# canset_pcb.net
KiCad netlist of a schematic drawn in EAGLE
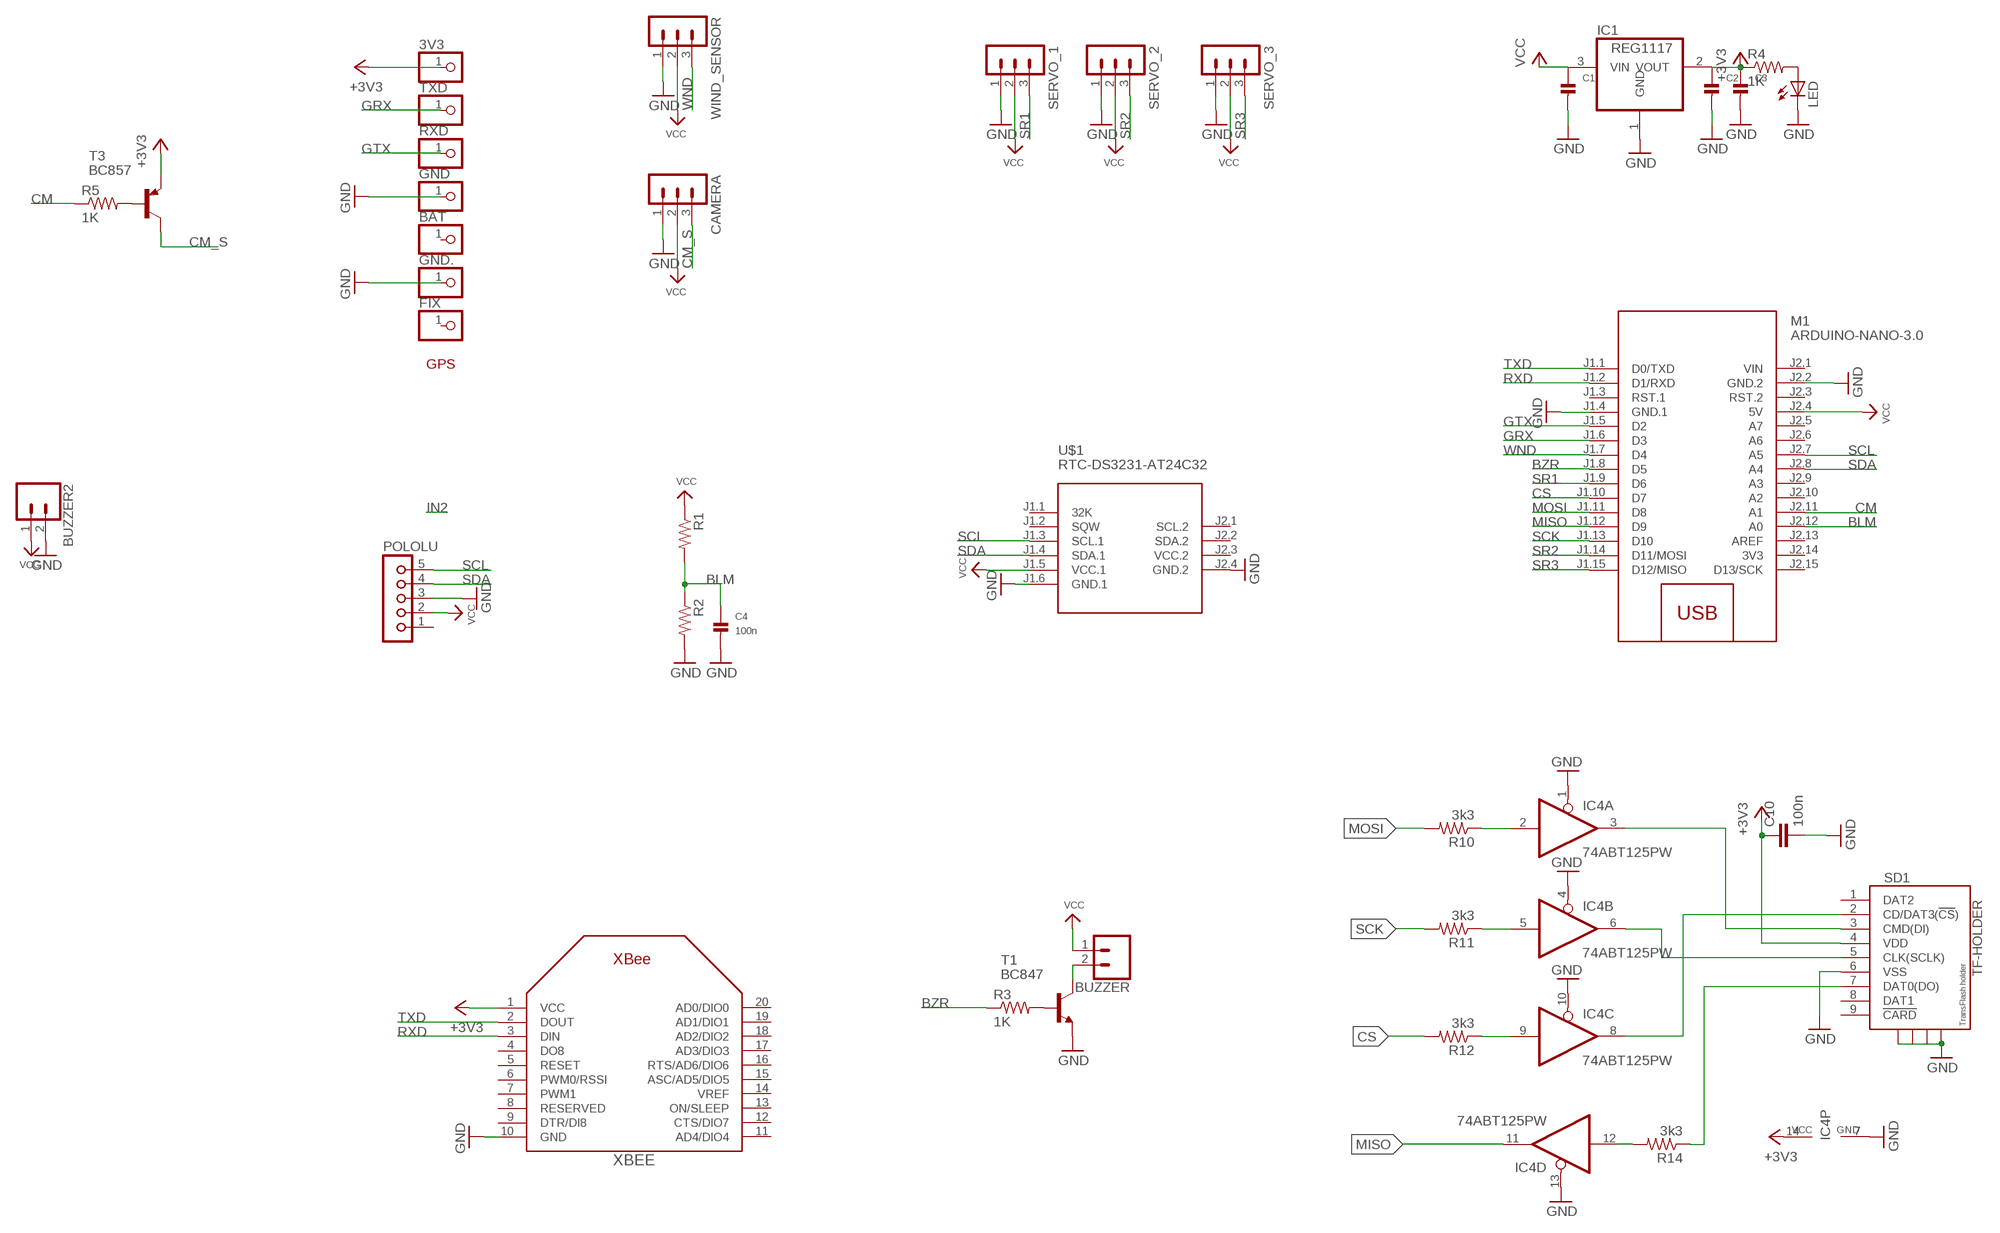
[diagram p0: schematic, sheet 1]

(export (version "E")
  (design (tool "Eeschema 10.0.6"))
  (components
    (comp (ref "3V3")
      (value "PINHD-1X1")
      (footprint "eagle-import:1X01")
      (libsource (lib "eagle-import") (part "PINHD-1X1"))
    )
    (comp (ref "BAT")
      (value "PINHD-1X1")
      (footprint "eagle-import:1X01")
      (libsource (lib "eagle-import") (part "PINHD-1X1"))
    )
    (comp (ref "BUZZER")
      (value "CONN_02")
      (footprint "eagle-import:1X02")
      (libsource (lib "eagle-import") (part "CONN_02"))
    )
    (comp (ref "BUZZER2")
      (value "CONN_02")
      (footprint "eagle-import:1X02")
      (libsource (lib "eagle-import") (part "CONN_02"))
    )
    (comp (ref "C1")
      (value "CAP_CERAMIC_0805")
      (footprint "eagle-import:_0805")
      (libsource (lib "eagle-import") (part "CAP_CERAMIC_0805"))
    )
    (comp (ref "C2")
      (value "CAP_CERAMIC_0805")
      (footprint "eagle-import:_0805")
      (libsource (lib "eagle-import") (part "CAP_CERAMIC_0805"))
    )
    (comp (ref "C3")
      (value "CAP_CERAMIC_0805")
      (footprint "eagle-import:_0805")
      (libsource (lib "eagle-import") (part "CAP_CERAMIC_0805"))
    )
    (comp (ref "C4")
      (value "100n")
      (footprint "eagle-import:_0805")
      (libsource (lib "eagle-import") (part "CAP_CERAMIC_0805"))
    )
    (comp (ref "C10")
      (value "100n")
      (footprint "eagle-import:C0603")
      (libsource (lib "eagle-import") (part "C-EUC0603"))
    )
    (comp (ref "CAMERA")
      (value "MA03-1")
      (footprint "eagle-import:MA03-1")
      (libsource (lib "eagle-import") (part "MA03-1"))
    )
    (comp (ref "FIX")
      (value "PINHD-1X1")
      (footprint "eagle-import:1X01")
      (libsource (lib "eagle-import") (part "PINHD-1X1"))
    )
    (comp (ref "GND")
      (value "PINHD-1X1")
      (footprint "eagle-import:1X01")
      (libsource (lib "eagle-import") (part "PINHD-1X1"))
    )
    (comp (ref "GND.")
      (value "PINHD-1X1")
      (footprint "eagle-import:1X01")
      (libsource (lib "eagle-import") (part "PINHD-1X1"))
    )
    (comp (ref "IC1")
      (value "REG1117")
      (footprint "eagle-import:SOT223")
      (libsource (lib "eagle-import") (part "REG1117"))
    )
    (comp (ref "IC4")
      (value "74ABT125PW")
      (footprint "eagle-import:TSSOP14")
      (libsource (lib "eagle-import") (part "74125PWABT"))
    )
    (comp (ref "LED")
      (value "LED5MM")
      (footprint "eagle-import:LED5MM")
      (libsource (lib "eagle-import") (part "LED5MM"))
    )
    (comp (ref "M1")
      (value "ARDUINO-NANO-3.0")
      (footprint "eagle-import:ARDUINO-NANO-3.0")
      (libsource (lib "eagle-import") (part "ARDUINO-NANO-3.0"))
    )
    (comp (ref "POLOLU")
      (value "JU05")
      (footprint "eagle-import:JU05")
      (libsource (lib "eagle-import") (part "JU05"))
    )
    (comp (ref "R1")
      (value "R-US_M0805")
      (footprint "eagle-import:M0805")
      (libsource (lib "eagle-import") (part "R-US_M0805"))
    )
    (comp (ref "R2")
      (value "R-US_M0805")
      (footprint "eagle-import:M0805")
      (libsource (lib "eagle-import") (part "R-US_M0805"))
    )
    (comp (ref "R3")
      (value "1K")
      (footprint "eagle-import:M0805")
      (libsource (lib "eagle-import") (part "R-US_M0805"))
    )
    (comp (ref "R4")
      (value "1K")
      (footprint "eagle-import:M0805")
      (libsource (lib "eagle-import") (part "R-US_M0805"))
    )
    (comp (ref "R5")
      (value "1K")
      (footprint "eagle-import:M0805")
      (libsource (lib "eagle-import") (part "R-US_M0805"))
    )
    (comp (ref "R10")
      (value "3k3")
      (footprint "eagle-import:R0603")
      (libsource (lib "eagle-import") (part "R-US_R0603"))
    )
    (comp (ref "R11")
      (value "3k3")
      (footprint "eagle-import:R0603")
      (libsource (lib "eagle-import") (part "R-US_R0603"))
    )
    (comp (ref "R12")
      (value "3k3")
      (footprint "eagle-import:R0603")
      (libsource (lib "eagle-import") (part "R-US_R0603"))
    )
    (comp (ref "R14")
      (value "3k3")
      (footprint "eagle-import:R0603")
      (libsource (lib "eagle-import") (part "R-US_R0603"))
    )
    (comp (ref "RXD")
      (value "PINHD-1X1")
      (footprint "eagle-import:1X01")
      (libsource (lib "eagle-import") (part "PINHD-1X1"))
    )
    (comp (ref "SD1")
      (value "TF-HOLDER")
      (footprint "eagle-import:TF-PULL")
      (libsource (lib "eagle-import") (part "TF-HOLDER"))
    )
    (comp (ref "SERVO_1")
      (value "MA03-1")
      (footprint "eagle-import:MA03-1")
      (libsource (lib "eagle-import") (part "MA03-1"))
    )
    (comp (ref "SERVO_2")
      (value "MA03-1")
      (footprint "eagle-import:MA03-1")
      (libsource (lib "eagle-import") (part "MA03-1"))
    )
    (comp (ref "SERVO_3")
      (value "MA03-1")
      (footprint "eagle-import:MA03-1")
      (libsource (lib "eagle-import") (part "MA03-1"))
    )
    (comp (ref "T1")
      (value "BC847")
      (footprint "eagle-import:SOT23")
      (libsource (lib "eagle-import") (part "BC847"))
    )
    (comp (ref "T3")
      (value "BC857")
      (footprint "eagle-import:SOT23")
      (libsource (lib "eagle-import") (part "BC857"))
    )
    (comp (ref "TXD")
      (value "PINHD-1X1")
      (footprint "eagle-import:1X01")
      (libsource (lib "eagle-import") (part "PINHD-1X1"))
    )
    (comp (ref "U$1")
      (value "RTC-DS3231-AT24C32")
      (footprint "eagle-import:RTC-DS3231-AT24C32")
      (libsource (lib "eagle-import") (part "RTC-DS3231-AT24C32"))
    )
    (comp (ref "WIND_SENSOR")
      (value "MA03-1")
      (footprint "eagle-import:MA03-1")
      (libsource (lib "eagle-import") (part "MA03-1"))
    )
    (comp (ref "XBEE")
      (value "XBEE")
      (footprint "eagle-import:XBEE")
      (libsource (lib "eagle-import") (part "XBEE"))
    )
  )
  (nets
    (net (code "1") (name "+3V3") (class "Default")
      (node (ref "3V3") (pin "1") (pinfunction "1_1") (pintype "passive"))
      (node (ref "C10") (pin "1") (pinfunction "1_1") (pintype "passive"))
      (node (ref "C2") (pin "1") (pinfunction "P$1_1") (pintype "passive"))
      (node (ref "C3") (pin "1") (pinfunction "P$1_1") (pintype "passive"))
      (node (ref "IC1") (pin "2") (pinfunction "VOUT_2") (pintype "output"))
      (node (ref "IC4") (pin "14") (pinfunction "VCC_14") (pintype "power_in"))
      (node (ref "R4") (pin "1") (pinfunction "1_1") (pintype "passive"))
      (node (ref "SD1") (pin "4") (pinfunction "VDD_4") (pintype "power_in"))
      (node (ref "T3") (pin "2") (pinfunction "E_2") (pintype "passive"))
      (node (ref "XBEE") (pin "1") (pinfunction "VCC_1") (pintype "power_in"))
    )
    (net (code "2") (name "/3V3") (class "Default")
      (node (ref "M1") (pin "J2.14") (pinfunction "3V3_J2.14") (pintype "power_in"))
    )
    (net (code "3") (name "/BLM") (class "Default")
      (node (ref "C4") (pin "1") (pinfunction "P$1_1") (pintype "passive"))
      (node (ref "M1") (pin "J2.12") (pinfunction "A0_J2.12") (pintype "bidirectional"))
      (node (ref "R1") (pin "2") (pinfunction "2_2") (pintype "passive"))
      (node (ref "R2") (pin "1") (pinfunction "1_1") (pintype "passive"))
    )
    (net (code "4") (name "/BZR") (class "Default")
      (node (ref "M1") (pin "J1.8") (pinfunction "D5_J1.8") (pintype "bidirectional"))
      (node (ref "R3") (pin "1") (pinfunction "1_1") (pintype "passive"))
    )
    (net (code "5") (name "/CM") (class "Default")
      (node (ref "M1") (pin "J2.11") (pinfunction "A1_J2.11") (pintype "bidirectional"))
      (node (ref "R5") (pin "1") (pinfunction "1_1") (pintype "passive"))
    )
    (net (code "6") (name "/CM_S") (class "Default")
      (node (ref "CAMERA") (pin "3") (pinfunction "3_3") (pintype "passive"))
      (node (ref "T3") (pin "3") (pinfunction "C_3") (pintype "passive"))
    )
    (net (code "7") (name "/GRX") (class "Default")
      (node (ref "M1") (pin "J1.6") (pinfunction "D3_J1.6") (pintype "bidirectional"))
      (node (ref "TXD") (pin "1") (pinfunction "1_1") (pintype "passive"))
    )
    (net (code "8") (name "/GTX") (class "Default")
      (node (ref "M1") (pin "J1.5") (pinfunction "D2_J1.5") (pintype "bidirectional"))
      (node (ref "RXD") (pin "1") (pinfunction "1_1") (pintype "passive"))
    )
    (net (code "10") (name "/RXD") (class "Default")
      (node (ref "M1") (pin "J1.2") (pinfunction "D1/RXD_J1.2") (pintype "bidirectional"))
      (node (ref "XBEE") (pin "3") (pinfunction "DIN_3") (pintype "input"))
    )
    (net (code "11") (name "/SCL") (class "Default")
      (node (ref "M1") (pin "J2.7") (pinfunction "A5_J2.7") (pintype "bidirectional"))
      (node (ref "POLOLU") (pin "5") (pinfunction "5_5") (pintype "passive"))
      (node (ref "U$1") (pin "J1.3") (pinfunction "SCL.1_J1.3") (pintype "bidirectional"))
    )
    (net (code "12") (name "/SDA") (class "Default")
      (node (ref "M1") (pin "J2.8") (pinfunction "A4_J2.8") (pintype "bidirectional"))
      (node (ref "POLOLU") (pin "4") (pinfunction "4_4") (pintype "passive"))
      (node (ref "U$1") (pin "J1.4") (pinfunction "SDA.1_J1.4") (pintype "bidirectional"))
    )
    (net (code "13") (name "/SR1") (class "Default")
      (node (ref "M1") (pin "J1.9") (pinfunction "D6_J1.9") (pintype "bidirectional"))
      (node (ref "SERVO_1") (pin "3") (pinfunction "3_3") (pintype "passive"))
    )
    (net (code "14") (name "/SR2") (class "Default")
      (node (ref "M1") (pin "J1.14") (pinfunction "D11/MOSI_J1.14") (pintype "bidirectional"))
      (node (ref "SERVO_2") (pin "3") (pinfunction "3_3") (pintype "passive"))
    )
    (net (code "15") (name "/SR3") (class "Default")
      (node (ref "M1") (pin "J1.15") (pinfunction "D12/MISO_J1.15") (pintype "bidirectional"))
      (node (ref "SERVO_3") (pin "3") (pinfunction "3_3") (pintype "passive"))
    )
    (net (code "16") (name "/TXD") (class "Default")
      (node (ref "M1") (pin "J1.1") (pinfunction "D0/TXD_J1.1") (pintype "bidirectional"))
      (node (ref "XBEE") (pin "2") (pinfunction "DOUT_2") (pintype "output"))
    )
    (net (code "17") (name "/VCC.2") (class "Default")
      (node (ref "U$1") (pin "J2.3") (pinfunction "VCC.2_J2.3") (pintype "power_in"))
    )
    (net (code "18") (name "/VIN") (class "Default")
      (node (ref "M1") (pin "J2.1") (pinfunction "VIN_J2.1") (pintype "power_in"))
    )
    (net (code "19") (name "/WND") (class "Default")
      (node (ref "M1") (pin "J1.7") (pinfunction "D4_J1.7") (pintype "bidirectional"))
      (node (ref "WIND_SENSOR") (pin "3") (pinfunction "3_3") (pintype "passive"))
    )
    (net (code "20") (name "CS") (class "Default")
      (node (ref "M1") (pin "J1.10") (pinfunction "D7_J1.10") (pintype "bidirectional"))
      (node (ref "R12") (pin "2") (pinfunction "2_2") (pintype "passive"))
    )
    (net (code "21") (name "GND") (class "Default")
      (node (ref "BUZZER2") (pin "2") (pinfunction "2_2") (pintype "passive"))
      (node (ref "C1") (pin "2") (pinfunction "P$2_2") (pintype "passive"))
      (node (ref "C10") (pin "2") (pinfunction "2_2") (pintype "passive"))
      (node (ref "C2") (pin "2") (pinfunction "P$2_2") (pintype "passive"))
      (node (ref "C3") (pin "2") (pinfunction "P$2_2") (pintype "passive"))
      (node (ref "C4") (pin "2") (pinfunction "P$2_2") (pintype "passive"))
      (node (ref "CAMERA") (pin "1") (pinfunction "1_1") (pintype "passive"))
      (node (ref "GND") (pin "1") (pinfunction "1_1") (pintype "passive"))
      (node (ref "GND.") (pin "1") (pinfunction "1_1") (pintype "passive"))
      (node (ref "IC1") (pin "1") (pinfunction "GND_1") (pintype "power_in"))
      (node (ref "IC4") (pin "1") (pinfunction "OE_1") (pintype "input"))
      (node (ref "IC4") (pin "10") (pinfunction "OE_10") (pintype "input"))
      (node (ref "IC4") (pin "13") (pinfunction "OE_13") (pintype "input"))
      (node (ref "IC4") (pin "4") (pinfunction "OE_4") (pintype "input"))
      (node (ref "IC4") (pin "7") (pinfunction "GND_7") (pintype "power_in"))
      (node (ref "LED") (pin "K") (pinfunction "C_K") (pintype "passive"))
      (node (ref "M1") (pin "J1.4") (pinfunction "GND.1_J1.4") (pintype "power_in"))
      (node (ref "M1") (pin "J2.2") (pinfunction "GND.2_J2.2") (pintype "power_in"))
      (node (ref "POLOLU") (pin "3") (pinfunction "3_3") (pintype "passive"))
      (node (ref "R2") (pin "2") (pinfunction "2_2") (pintype "passive"))
      (node (ref "SD1") (pin "6") (pinfunction "VSS_6") (pintype "power_in"))
      (node (ref "SD1") (pin "S1") (pinfunction "S1_S1") (pintype "passive"))
      (node (ref "SD1") (pin "S2") (pinfunction "S2_S2") (pintype "passive"))
      (node (ref "SD1") (pin "S3") (pinfunction "S3_S3") (pintype "passive"))
      (node (ref "SD1") (pin "S4") (pinfunction "S4_S4") (pintype "passive"))
      (node (ref "SERVO_1") (pin "1") (pinfunction "1_1") (pintype "passive"))
      (node (ref "SERVO_2") (pin "1") (pinfunction "1_1") (pintype "passive"))
      (node (ref "SERVO_3") (pin "1") (pinfunction "1_1") (pintype "passive"))
      (node (ref "T1") (pin "2") (pinfunction "E_2") (pintype "passive"))
      (node (ref "U$1") (pin "J1.6") (pinfunction "GND.1_J1.6") (pintype "power_in"))
      (node (ref "U$1") (pin "J2.4") (pinfunction "GND.2_J2.4") (pintype "power_in"))
      (node (ref "WIND_SENSOR") (pin "1") (pinfunction "1_1") (pintype "passive"))
      (node (ref "XBEE") (pin "10") (pinfunction "GND_10") (pintype "power_in"))
    )
    (net (code "22") (name "MISO") (class "Default")
      (node (ref "IC4") (pin "11") (pinfunction "O_11") (pintype "tri_state"))
      (node (ref "M1") (pin "J1.12") (pinfunction "D9_J1.12") (pintype "bidirectional"))
    )
    (net (code "23") (name "MOSI") (class "Default")
      (node (ref "M1") (pin "J1.11") (pinfunction "D8_J1.11") (pintype "bidirectional"))
      (node (ref "R10") (pin "2") (pinfunction "2_2") (pintype "passive"))
    )
    (net (code "24") (name "Net-(IC4A-I)") (class "Default")
      (node (ref "IC4") (pin "2") (pinfunction "I_2") (pintype "input"))
      (node (ref "R10") (pin "1") (pinfunction "1_1") (pintype "passive"))
    )
    (net (code "25") (name "Net-(IC4A-O)") (class "Default")
      (node (ref "IC4") (pin "3") (pinfunction "O_3") (pintype "tri_state"))
      (node (ref "SD1") (pin "3") (pinfunction "CMD(DI)_3") (pintype "bidirectional"))
    )
    (net (code "26") (name "Net-(IC4B-I)") (class "Default")
      (node (ref "IC4") (pin "5") (pinfunction "I_5") (pintype "input"))
      (node (ref "R11") (pin "1") (pinfunction "1_1") (pintype "passive"))
    )
    (net (code "27") (name "Net-(IC4B-O)") (class "Default")
      (node (ref "IC4") (pin "6") (pinfunction "O_6") (pintype "tri_state"))
      (node (ref "SD1") (pin "5") (pinfunction "CLK(SCLK)_5") (pintype "input"))
    )
    (net (code "28") (name "Net-(IC4C-I)") (class "Default")
      (node (ref "IC4") (pin "9") (pinfunction "I_9") (pintype "input"))
      (node (ref "R12") (pin "1") (pinfunction "1_1") (pintype "passive"))
    )
    (net (code "29") (name "Net-(IC4C-O)") (class "Default")
      (node (ref "IC4") (pin "8") (pinfunction "O_8") (pintype "tri_state"))
      (node (ref "SD1") (pin "2") (pinfunction "CD/DAT3(~{CS})_2") (pintype "bidirectional"))
    )
    (net (code "30") (name "Net-(IC4D-I)") (class "Default")
      (node (ref "IC4") (pin "12") (pinfunction "I_12") (pintype "input"))
      (node (ref "R14") (pin "2") (pinfunction "2_2") (pintype "passive"))
    )
    (net (code "31") (name "Net-(LED-PadA)") (class "Default")
      (node (ref "LED") (pin "A") (pinfunction "A_A") (pintype "passive"))
      (node (ref "R4") (pin "2") (pinfunction "2_2") (pintype "passive"))
    )
    (net (code "32") (name "Net-(SD1-DAT0(DO))") (class "Default")
      (node (ref "R14") (pin "1") (pinfunction "1_1") (pintype "passive"))
      (node (ref "SD1") (pin "7") (pinfunction "DAT0(DO)_7") (pintype "bidirectional"))
    )
    (net (code "33") (name "Net-(T1-B)") (class "Default")
      (node (ref "R3") (pin "2") (pinfunction "2_2") (pintype "passive"))
      (node (ref "T1") (pin "1") (pinfunction "B_1") (pintype "passive"))
    )
    (net (code "34") (name "Net-(T1-C)") (class "Default")
      (node (ref "BUZZER") (pin "2") (pinfunction "2_2") (pintype "passive"))
      (node (ref "T1") (pin "3") (pinfunction "C_3") (pintype "passive"))
    )
    (net (code "35") (name "Net-(T3-B)") (class "Default")
      (node (ref "R5") (pin "2") (pinfunction "2_2") (pintype "passive"))
      (node (ref "T3") (pin "1") (pinfunction "B_1") (pintype "passive"))
    )
    (net (code "36") (name "SCK") (class "Default")
      (node (ref "M1") (pin "J1.13") (pinfunction "D10_J1.13") (pintype "bidirectional"))
      (node (ref "R11") (pin "2") (pinfunction "2_2") (pintype "passive"))
    )
    (net (code "37") (name "VCC") (class "Default")
      (node (ref "BUZZER") (pin "1") (pinfunction "1_1") (pintype "passive"))
      (node (ref "BUZZER2") (pin "1") (pinfunction "1_1") (pintype "passive"))
      (node (ref "C1") (pin "1") (pinfunction "P$1_1") (pintype "passive"))
      (node (ref "CAMERA") (pin "2") (pinfunction "2_2") (pintype "passive"))
      (node (ref "IC1") (pin "3") (pinfunction "VIN_3") (pintype "input"))
      (node (ref "M1") (pin "J2.4") (pinfunction "5V_J2.4") (pintype "power_in"))
      (node (ref "POLOLU") (pin "2") (pinfunction "2_2") (pintype "passive"))
      (node (ref "R1") (pin "1") (pinfunction "1_1") (pintype "passive"))
      (node (ref "SERVO_1") (pin "2") (pinfunction "2_2") (pintype "passive"))
      (node (ref "SERVO_2") (pin "2") (pinfunction "2_2") (pintype "passive"))
      (node (ref "SERVO_3") (pin "2") (pinfunction "2_2") (pintype "passive"))
      (node (ref "U$1") (pin "J1.5") (pinfunction "VCC.1_J1.5") (pintype "power_in"))
      (node (ref "WIND_SENSOR") (pin "2") (pinfunction "2_2") (pintype "passive"))
    )
    (net (code "38") (name "unconnected-(BAT-Pad1)") (class "Default")
      (node (ref "BAT") (pin "1") (pinfunction "1_1") (pintype "passive"))
    )
    (net (code "39") (name "unconnected-(FIX-Pad1)") (class "Default")
      (node (ref "FIX") (pin "1") (pinfunction "1_1") (pintype "passive"))
    )
    (net (code "40") (name "unconnected-(M1-A2-PadJ2.10)") (class "Default")
      (node (ref "M1") (pin "J2.10") (pinfunction "A2_J2.10") (pintype "bidirectional"))
    )
    (net (code "41") (name "unconnected-(M1-A3-PadJ2.9)") (class "Default")
      (node (ref "M1") (pin "J2.9") (pinfunction "A3_J2.9") (pintype "bidirectional"))
    )
    (net (code "42") (name "unconnected-(M1-A6-PadJ2.6)") (class "Default")
      (node (ref "M1") (pin "J2.6") (pinfunction "A6_J2.6") (pintype "bidirectional"))
    )
    (net (code "43") (name "unconnected-(M1-A7-PadJ2.5)") (class "Default")
      (node (ref "M1") (pin "J2.5") (pinfunction "A7_J2.5") (pintype "bidirectional"))
    )
    (net (code "44") (name "unconnected-(M1-AREF-PadJ2.13)") (class "Default")
      (node (ref "M1") (pin "J2.13") (pinfunction "AREF_J2.13") (pintype "bidirectional"))
    )
    (net (code "45") (name "unconnected-(M1-D13{slash}SCK-PadJ2.15)") (class "Default")
      (node (ref "M1") (pin "J2.15") (pinfunction "D13/SCK_J2.15") (pintype "bidirectional"))
    )
    (net (code "46") (name "unconnected-(M1-RST.1-PadJ1.3)") (class "Default")
      (node (ref "M1") (pin "J1.3") (pinfunction "RST.1_J1.3") (pintype "bidirectional"))
    )
    (net (code "47") (name "unconnected-(M1-RST.2-PadJ2.3)") (class "Default")
      (node (ref "M1") (pin "J2.3") (pinfunction "RST.2_J2.3") (pintype "bidirectional"))
    )
    (net (code "48") (name "unconnected-(POLOLU-Pad1)") (class "Default")
      (node (ref "POLOLU") (pin "1") (pinfunction "1_1") (pintype "passive"))
    )
    (net (code "49") (name "unconnected-(SD1-DAT1-Pad8)") (class "Default")
      (node (ref "SD1") (pin "8") (pinfunction "DAT1_8") (pintype "bidirectional"))
    )
    (net (code "50") (name "unconnected-(SD1-DAT2-Pad1)") (class "Default")
      (node (ref "SD1") (pin "1") (pinfunction "DAT2_1") (pintype "bidirectional"))
    )
    (net (code "51") (name "unconnected-(SD1-~{CARD}-Pad9)") (class "Default")
      (node (ref "SD1") (pin "9") (pinfunction "~{CARD}_9") (pintype "passive"))
    )
    (net (code "52") (name "unconnected-(U$1-32K-PadJ1.1)") (class "Default")
      (node (ref "U$1") (pin "J1.1") (pinfunction "32K_J1.1") (pintype "bidirectional"))
    )
    (net (code "53") (name "unconnected-(U$1-SCL.2-PadJ2.1)") (class "Default")
      (node (ref "U$1") (pin "J2.1") (pinfunction "SCL.2_J2.1") (pintype "bidirectional"))
    )
    (net (code "54") (name "unconnected-(U$1-SDA.2-PadJ2.2)") (class "Default")
      (node (ref "U$1") (pin "J2.2") (pinfunction "SDA.2_J2.2") (pintype "bidirectional"))
    )
    (net (code "55") (name "unconnected-(U$1-SQW-PadJ1.2)") (class "Default")
      (node (ref "U$1") (pin "J1.2") (pinfunction "SQW_J1.2") (pintype "bidirectional"))
    )
    (net (code "56") (name "unconnected-(XBEE-AD0{slash}DIO0-Pad20)") (class "Default")
      (node (ref "XBEE") (pin "20") (pinfunction "AD0/DIO0_20") (pintype "bidirectional"))
    )
    (net (code "57") (name "unconnected-(XBEE-AD1{slash}DIO1-Pad19)") (class "Default")
      (node (ref "XBEE") (pin "19") (pinfunction "AD1/DIO1_19") (pintype "bidirectional"))
    )
    (net (code "58") (name "unconnected-(XBEE-AD2{slash}DIO2-Pad18)") (class "Default")
      (node (ref "XBEE") (pin "18") (pinfunction "AD2/DIO2_18") (pintype "bidirectional"))
    )
    (net (code "59") (name "unconnected-(XBEE-AD3{slash}DIO3-Pad17)") (class "Default")
      (node (ref "XBEE") (pin "17") (pinfunction "AD3/DIO3_17") (pintype "bidirectional"))
    )
    (net (code "60") (name "unconnected-(XBEE-AD4{slash}DIO4-Pad11)") (class "Default")
      (node (ref "XBEE") (pin "11") (pinfunction "AD4/DIO4_11") (pintype "bidirectional"))
    )
    (net (code "61") (name "unconnected-(XBEE-ASC{slash}AD5{slash}DIO5-Pad15)") (class "Default")
      (node (ref "XBEE") (pin "15") (pinfunction "ASC/AD5/DIO5_15") (pintype "bidirectional"))
    )
    (net (code "62") (name "unconnected-(XBEE-CTS{slash}DIO7-Pad12)") (class "Default")
      (node (ref "XBEE") (pin "12") (pinfunction "CTS/DIO7_12") (pintype "bidirectional"))
    )
    (net (code "63") (name "unconnected-(XBEE-DO8-Pad4)") (class "Default")
      (node (ref "XBEE") (pin "4") (pinfunction "DO8_4") (pintype "output"))
    )
    (net (code "64") (name "unconnected-(XBEE-DTR{slash}DI8-Pad9)") (class "Default")
      (node (ref "XBEE") (pin "9") (pinfunction "DTR/DI8_9") (pintype "input"))
    )
    (net (code "65") (name "unconnected-(XBEE-ON{slash}SLEEP-Pad13)") (class "Default")
      (node (ref "XBEE") (pin "13") (pinfunction "ON/SLEEP_13") (pintype "output"))
    )
    (net (code "66") (name "unconnected-(XBEE-PWM0{slash}RSSI-Pad6)") (class "Default")
      (node (ref "XBEE") (pin "6") (pinfunction "PWM0/RSSI_6") (pintype "output"))
    )
    (net (code "67") (name "unconnected-(XBEE-PWM1-Pad7)") (class "Default")
      (node (ref "XBEE") (pin "7") (pinfunction "PWM1_7") (pintype "output"))
    )
    (net (code "68") (name "unconnected-(XBEE-RESERVED-Pad8)") (class "Default")
      (node (ref "XBEE") (pin "8") (pinfunction "RESERVED_8") (pintype "no_connect"))
    )
    (net (code "69") (name "unconnected-(XBEE-RESET-Pad5)") (class "Default")
      (node (ref "XBEE") (pin "5") (pinfunction "RESET_5") (pintype "input"))
    )
    (net (code "70") (name "unconnected-(XBEE-RTS{slash}AD6{slash}DIO6-Pad16)") (class "Default")
      (node (ref "XBEE") (pin "16") (pinfunction "RTS/AD6/DIO6_16") (pintype "bidirectional"))
    )
    (net (code "71") (name "unconnected-(XBEE-VREF-Pad14)") (class "Default")
      (node (ref "XBEE") (pin "14") (pinfunction "VREF_14") (pintype "input"))
    )
  )
)
